# GP_Power_Circuit_Sheet.net
KiCad netlist of a schematic drawn in Altium Designer
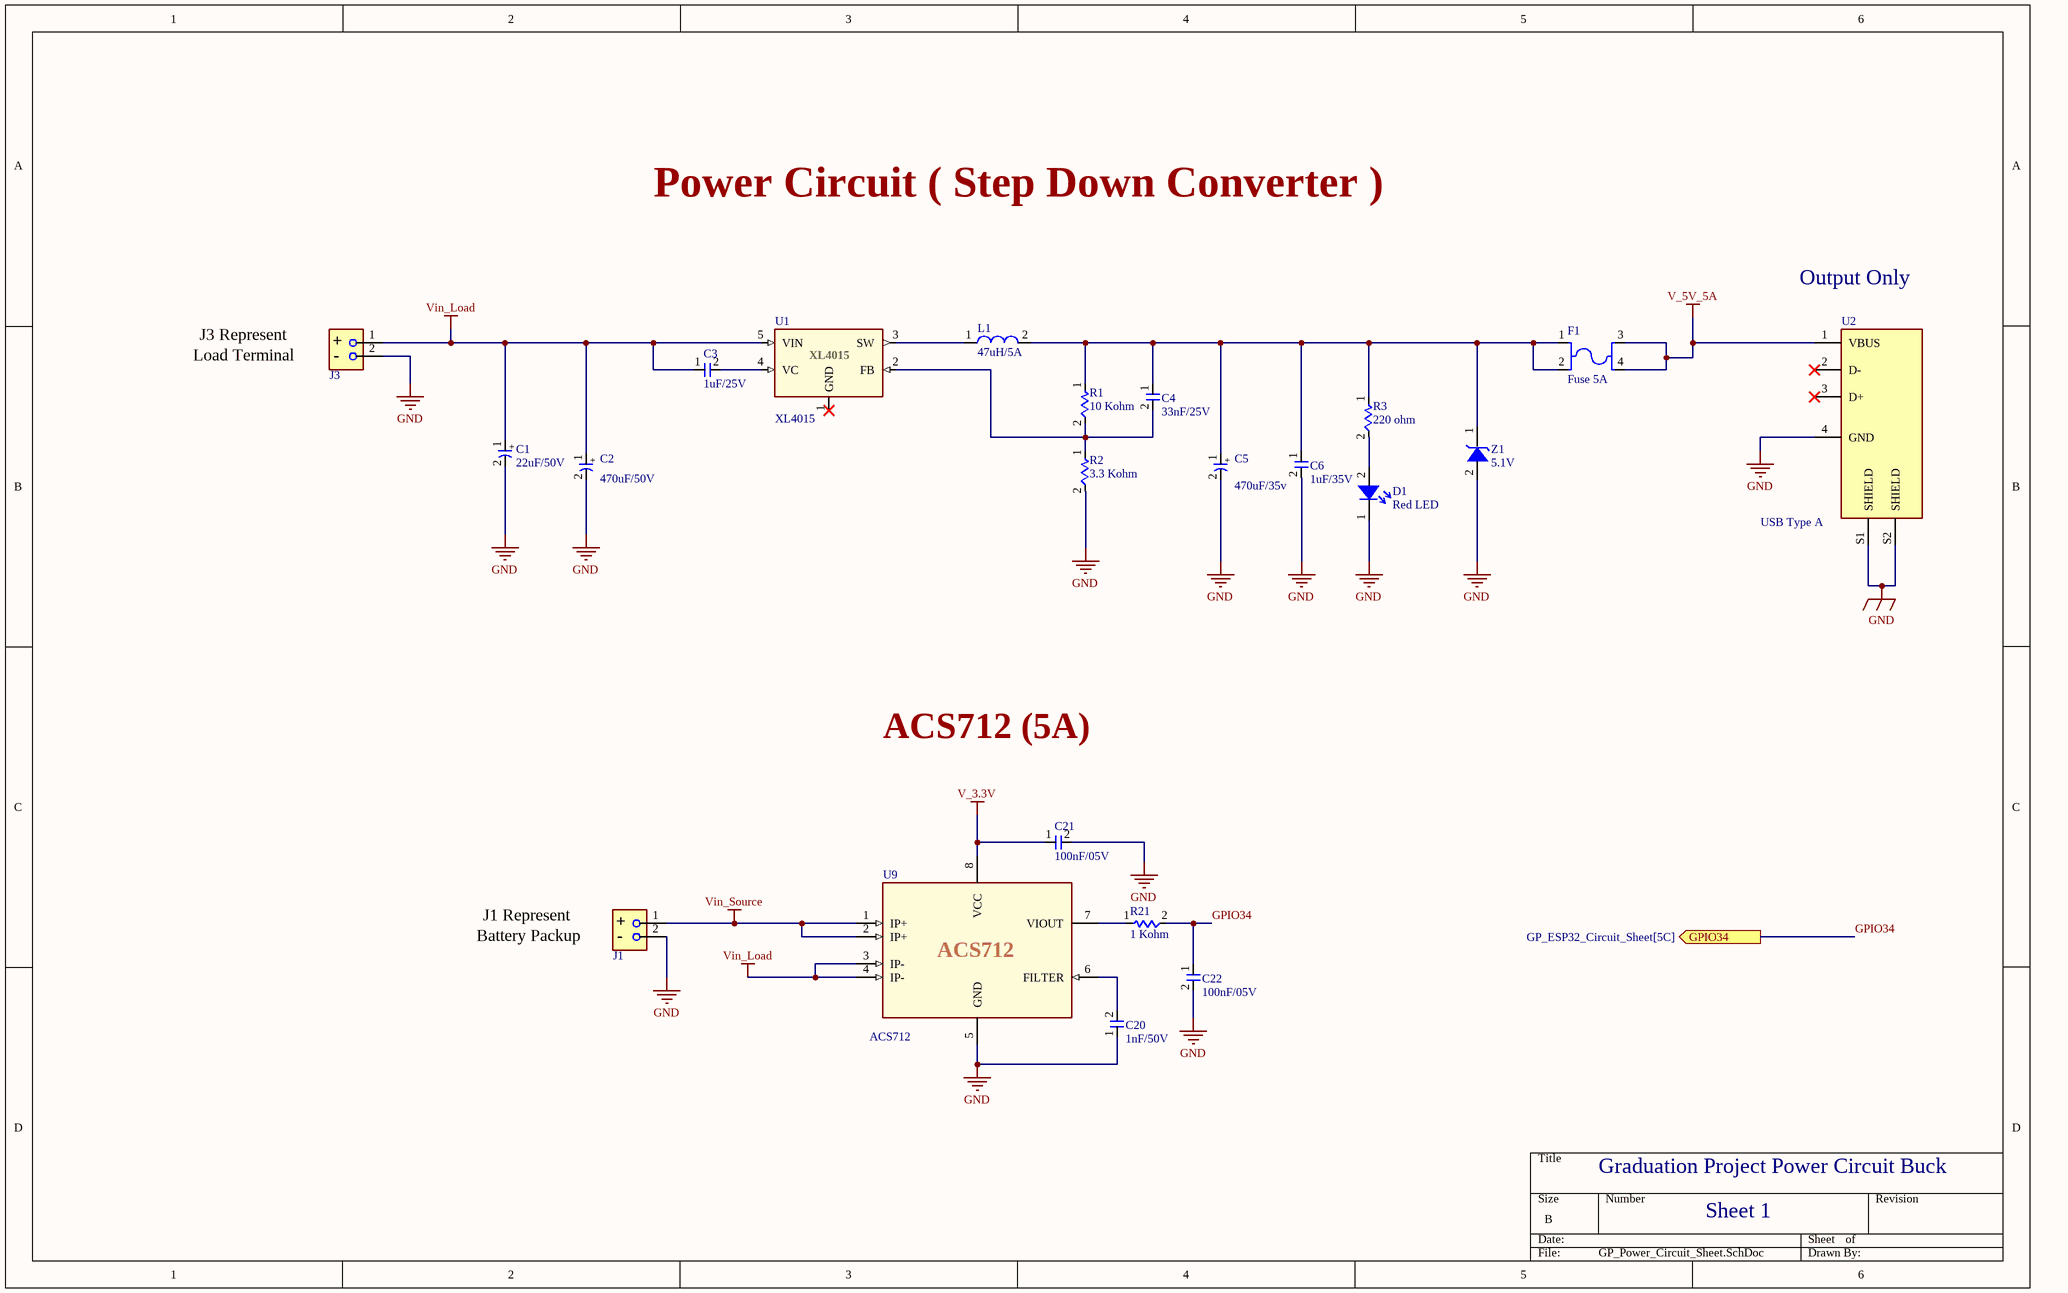
[diagram p0: GP_Power_Circuit_Sheet.SchDoc]

(export (version "E")
  (design (tool "Eeschema 10.0.6"))
  (components
    (comp (ref "C1")
      (value "22uF/50V")
      (footprint "Electrolytic Capacitor 22UF")
      (description "Electrolytic Capacitor (22UF , 35V)SMD Radial Electrolytic Capacitor")
      (libsource (lib "GP_Integrated_Library") (part "Electrolytic Capacitor 22UF"))
    )
    (comp (ref "C2")
      (value "470uF/50V")
      (footprint "Capacitor 470uF/50v")
      (description "Electrolytic Capacitor (470UF , 50V)")
      (libsource (lib "GP_Integrated_Library") (part "Capacitor 470uF/50v"))
    )
    (comp (ref "C3")
      (value "1uF/25V")
      (footprint "Capacitor 1uF (1206)")
      (description "Ceramic Capacitor (1uF , 50V) SMD (1206)")
      (libsource (lib "GP_Integrated_Library") (part "Capacitor 1uF"))
    )
    (comp (ref "C4")
      (value "33nF/25V")
      (footprint "Capacitor 33nF")
      (description "Smd Chip Capacitor size 1206 33nF")
      (libsource (lib "GP_Integrated_Library") (part "Capacitor 33nF"))
    )
    (comp (ref "C5")
      (value "470uF/35v")
      (footprint "Capacitor 470uF/35v")
      (description "Electrolytic Capacitor (470UF , 35V)")
      (libsource (lib "GP_Integrated_Library") (part "Capacitor 470uF/35v"))
    )
    (comp (ref "C6")
      (value "1uF/35V")
      (footprint "Capacitor 1uF (1206)")
      (description "Ceramic Capacitor (1uF , 50V) SMD (1206)")
      (libsource (lib "GP_Integrated_Library") (part "Capacitor 1uF"))
    )
    (comp (ref "C20")
      (value "1nF/50V")
      (footprint "Capacitor 1nF")
      (description "Smd Chip Capacitor size 1206 1nF)")
      (libsource (lib "GP_Integrated_Library") (part "Capacitor 1nF"))
    )
    (comp (ref "C21")
      (value "100nF/05V")
      (footprint "Capacitor 1uF (1206)")
      (description "Ceramic Capacitor (1uF , 50V) SMD (1206)")
      (libsource (lib "GP_Integrated_Library") (part "Capacitor 1uF"))
    )
    (comp (ref "C22")
      (value "100nF/05V")
      (footprint "Capacitor 1uF (1206)")
      (description "Ceramic Capacitor (1uF , 50V) SMD (1206)")
      (libsource (lib "GP_Integrated_Library") (part "Capacitor 1uF"))
    )
    (comp (ref "D1")
      (value "Red LED")
      (footprint "Red Led")
      (description "2012 Smd Led Red")
      (libsource (lib "GP_Integrated_Library") (part "Red LED"))
    )
    (comp (ref "F1")
      (value "Fuse 5A")
      (footprint "Fuse 5A")
      (description "Glass Fuse T5 (5A-250V)")
      (libsource (lib "GP_Integrated_Library") (part "Fuse 5A"))
    )
    (comp (ref "J1")
      (value "terminal block connector")
      (footprint "Battery Connector")
      (description "2-Pole 5mm Pitch PCB Mount Screw TermInal Block 8A 250V")
      (libsource (lib "GP_Integrated_Library") (part "Terminal Block"))
    )
    (comp (ref "J3")
      (value "terminal block connector")
      (footprint "Battery Connector")
      (description "2-Pole 5mm Pitch PCB Mount Screw TermInal Block 8A 250V")
      (libsource (lib "GP_Integrated_Library") (part "Terminal Block"))
    )
    (comp (ref "L1")
      (value "47uH/5A")
      (footprint "Inductor")
      (libsource (lib "GP_Integrated_Library") (part "Inductor 47uH/5A"))
    )
    (comp (ref "R1")
      (value "10 Kohm")
      (footprint "Resistor 1Kohm")
      (description "SMD RESISTORS 200V-500V 1206")
      (libsource (lib "GP_Integrated_Library") (part "Resistor 1 Kohm"))
    )
    (comp (ref "R2")
      (value "3.3 Kohm")
      (footprint "Resistor 1Kohm")
      (description "SMD RESISTORS 200V-500V 1206")
      (libsource (lib "GP_Integrated_Library") (part "Resistor 1 Kohm"))
    )
    (comp (ref "R3")
      (value "220 ohm")
      (footprint "Resistor 1Kohm")
      (description "SMD RESISTORS 200V-500V 1206")
      (libsource (lib "GP_Integrated_Library") (part "Resistor 1 Kohm"))
    )
    (comp (ref "R21")
      (value "1 Kohm")
      (footprint "Resistor 1Kohm")
      (description "SMD RESISTORS 200V-500V 1206")
      (libsource (lib "GP_Integrated_Library") (part "Resistor 1 Kohm"))
    )
    (comp (ref "U1")
      (value "XL4015")
      (footprint "XL4015")
      (description "XL4015 Step Down Module (5A) Constant Current / Voltage LED Drives Lithium Battery Charging Module")
      (libsource (lib "GP_Integrated_Library") (part "XL4015"))
    )
    (comp (ref "U2")
      (value "USB Type A")
      (footprint "USB Type A")
      (libsource (lib "GP_Integrated_Library") (part "USB Type A"))
    )
    (comp (ref "U9")
      (value "ACS712")
      (footprint "ACS712")
      (description "AC/DC Current Sensor Module ACS712 (5A)")
      (libsource (lib "GP_Integrated_Library") (part "ACS712"))
    )
    (comp (ref "Z1")
      (value "5.1V")
      (footprint "Zener Diode")
      (description "Zener Diodes ( 5.1V , 0.5w )")
      (libsource (lib "GP_Integrated_Library") (part "Zener 5.1V"))
    )
  )
  (nets
    (net (code "1") (name "/GPIO34") (class "Default")
      (node (ref "C22") (pin "1") (pinfunction "Pin_1_1") (pintype "passive"))
      (node (ref "R21") (pin "2") (pinfunction "pin_2_2") (pintype "passive"))
    )
    (net (code "2") (name "GND") (class "Default")
      (node (ref "C1") (pin "2") (pinfunction "Pin_2_2") (pintype "passive"))
      (node (ref "C2") (pin "2") (pinfunction "Pin_2_2") (pintype "passive"))
      (node (ref "C20") (pin "1") (pinfunction "Pin_1_1") (pintype "passive"))
      (node (ref "C21") (pin "2") (pinfunction "Pin_2_2") (pintype "passive"))
      (node (ref "C22") (pin "2") (pinfunction "Pin_2_2") (pintype "passive"))
      (node (ref "C5") (pin "2") (pinfunction "Pin_2_2") (pintype "passive"))
      (node (ref "C6") (pin "2") (pinfunction "Pin_2_2") (pintype "passive"))
      (node (ref "D1") (pin "1") (pintype "passive"))
      (node (ref "J1") (pin "2") (pinfunction "2_2") (pintype "passive"))
      (node (ref "J3") (pin "2") (pinfunction "2_2") (pintype "passive"))
      (node (ref "R2") (pin "2") (pinfunction "pin_2_2") (pintype "passive"))
      (node (ref "U2") (pin "4") (pinfunction "GND_4") (pintype "passive"))
      (node (ref "U2") (pin "S1") (pinfunction "SHIELD_S1") (pintype "passive"))
      (node (ref "U2") (pin "S2") (pinfunction "SHIELD_S2") (pintype "passive"))
      (node (ref "U9") (pin "5") (pinfunction "GND_5") (pintype "power_in"))
      (node (ref "Z1") (pin "2") (pintype "passive"))
    )
    (net (code "3") (name "Net-(C3-Pin_2)") (class "Default")
      (node (ref "C3") (pin "2") (pinfunction "Pin_2_2") (pintype "passive"))
      (node (ref "U1") (pin "4") (pinfunction "VC_4") (pintype "input"))
    )
    (net (code "4") (name "Net-(C4-Pin_1)") (class "Default")
      (node (ref "C4") (pin "1") (pinfunction "Pin_1_1") (pintype "passive"))
      (node (ref "C5") (pin "1") (pinfunction "Pin_1_1") (pintype "passive"))
      (node (ref "C6") (pin "1") (pinfunction "Pin_1_1") (pintype "passive"))
      (node (ref "F1") (pin "1") (pinfunction "Pin_1_1") (pintype "passive"))
      (node (ref "F1") (pin "2") (pinfunction "Pin_2_2") (pintype "passive"))
      (node (ref "L1") (pin "2") (pinfunction "11_2") (pintype "passive"))
      (node (ref "R1") (pin "1") (pinfunction "Pin_1_1") (pintype "passive"))
      (node (ref "R3") (pin "1") (pinfunction "Pin_1_1") (pintype "passive"))
      (node (ref "Z1") (pin "1") (pintype "passive"))
    )
    (net (code "5") (name "Net-(C4-Pin_2)") (class "Default")
      (node (ref "C4") (pin "2") (pinfunction "Pin_2_2") (pintype "passive"))
      (node (ref "R1") (pin "2") (pinfunction "pin_2_2") (pintype "passive"))
      (node (ref "R2") (pin "1") (pinfunction "Pin_1_1") (pintype "passive"))
      (node (ref "U1") (pin "2") (pinfunction "FB_2") (pintype "input"))
    )
    (net (code "6") (name "Net-(C20-Pin_2)") (class "Default")
      (node (ref "C20") (pin "2") (pinfunction "Pin_2_2") (pintype "passive"))
      (node (ref "U9") (pin "6") (pinfunction "FILTER_6") (pintype "input"))
    )
    (net (code "7") (name "Net-(R3-pin_2)") (class "Default")
      (node (ref "D1") (pin "2") (pintype "passive"))
      (node (ref "R3") (pin "2") (pinfunction "pin_2_2") (pintype "passive"))
    )
    (net (code "8") (name "Net-(R21-Pin_1)") (class "Default")
      (node (ref "R21") (pin "1") (pinfunction "Pin_1_1") (pintype "passive"))
      (node (ref "U9") (pin "7") (pinfunction "VIOUT_7") (pintype "passive"))
    )
    (net (code "9") (name "Net-(U1-SW)") (class "Default")
      (node (ref "L1") (pin "1") (pinfunction "11_1") (pintype "passive"))
      (node (ref "U1") (pin "3") (pinfunction "SW_3") (pintype "output"))
    )
    (net (code "10") (name "V_3.3V") (class "Default")
      (node (ref "C21") (pin "1") (pinfunction "Pin_1_1") (pintype "passive"))
      (node (ref "U9") (pin "8") (pinfunction "VCC_8") (pintype "power_in"))
    )
    (net (code "11") (name "V_5V_5A") (class "Default")
      (node (ref "F1") (pin "3") (pinfunction "Pin_2_3") (pintype "passive"))
      (node (ref "F1") (pin "4") (pinfunction "Pin_1_4") (pintype "passive"))
      (node (ref "U2") (pin "1") (pinfunction "VBUS_1") (pintype "power_in"))
    )
    (net (code "12") (name "Vin_Load") (class "Default")
      (node (ref "C1") (pin "1") (pinfunction "Pin_1_1") (pintype "passive"))
      (node (ref "C2") (pin "1") (pinfunction "Pin_1_1") (pintype "passive"))
      (node (ref "C3") (pin "1") (pinfunction "Pin_1_1") (pintype "passive"))
      (node (ref "J3") (pin "1") (pinfunction "2_1") (pintype "passive"))
      (node (ref "U1") (pin "5") (pinfunction "VIN_5") (pintype "input"))
      (node (ref "U9") (pin "3") (pinfunction "IP-_3") (pintype "input"))
      (node (ref "U9") (pin "4") (pinfunction "IP-_4") (pintype "input"))
    )
    (net (code "13") (name "Vin_Source") (class "Default")
      (node (ref "J1") (pin "1") (pinfunction "2_1") (pintype "passive"))
      (node (ref "U9") (pin "1") (pinfunction "IP+_1") (pintype "input"))
      (node (ref "U9") (pin "2") (pinfunction "IP+_2") (pintype "input"))
    )
    (net (code "14") (name "unconnected-(U1-GND-Pad1)") (class "Default")
      (node (ref "U1") (pin "1") (pinfunction "GND_1") (pintype "power_in+no_connect"))
    )
    (net (code "15") (name "unconnected-(U2-D+-Pad3)") (class "Default")
      (node (ref "U2") (pin "3") (pinfunction "D+_3") (pintype "passive+no_connect"))
    )
    (net (code "16") (name "unconnected-(U2-D--Pad2)") (class "Default")
      (node (ref "U2") (pin "2") (pinfunction "D-_2") (pintype "power_in+no_connect"))
    )
  )
)
